# BlueCore_TM_3-Multuimedia_small.net
KiCad netlist of a schematic drawn in EAGLE
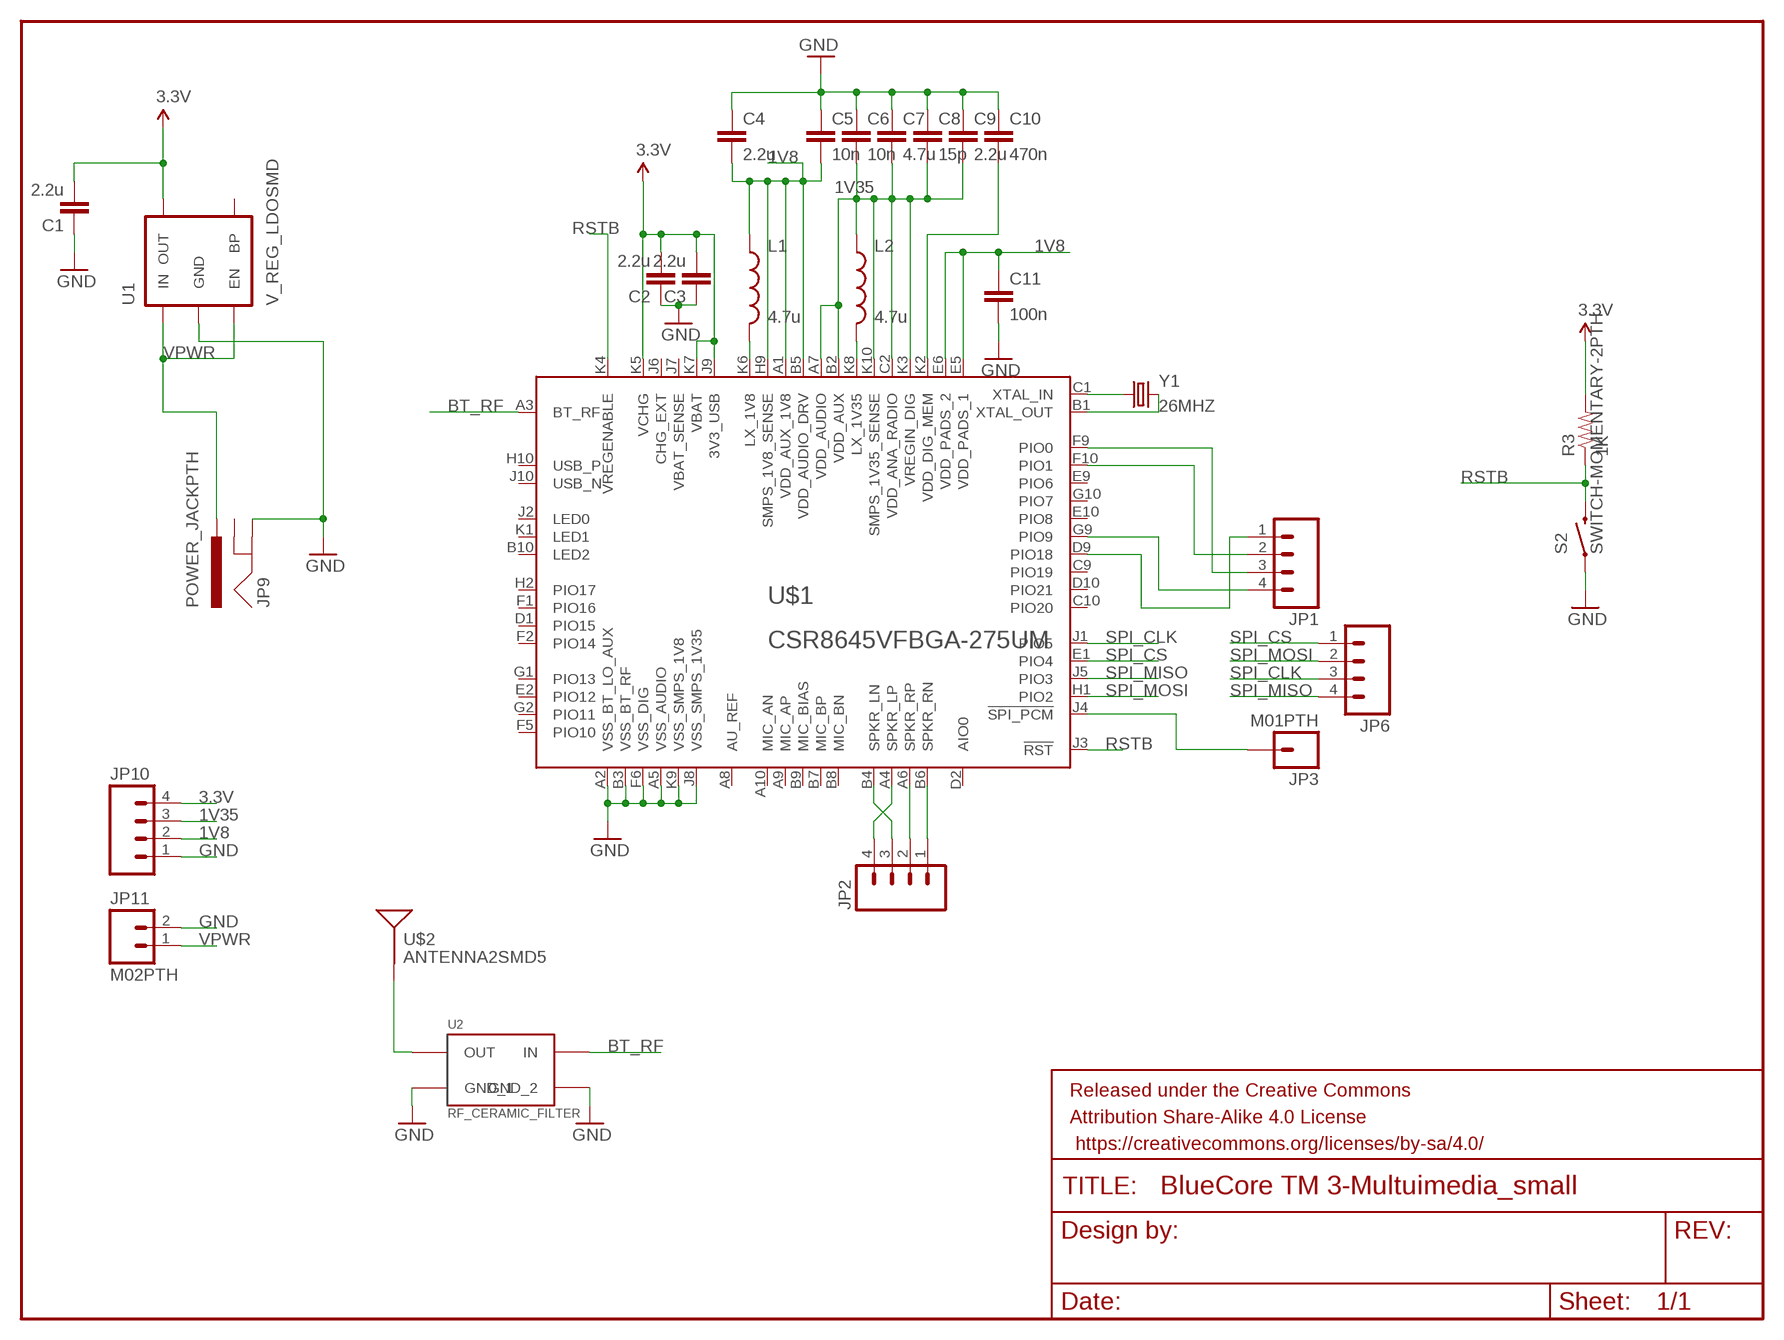
[diagram p0: schematic, sheet 1]

(export (version "E")
  (design (tool "Eeschema 10.0.6"))
  (components
    (comp (ref "C1")
      (value "2.2u")
      (footprint "eagle-import:CAP-PTH-SMALL")
      (libsource (lib "eagle-import") (part "CAPPTH"))
    )
    (comp (ref "C2")
      (value "2.2u")
      (footprint "eagle-import:CAP-PTH-SMALL")
      (libsource (lib "eagle-import") (part "CAPPTH"))
    )
    (comp (ref "C3")
      (value "2.2u")
      (footprint "eagle-import:CAP-PTH-SMALL")
      (libsource (lib "eagle-import") (part "CAPPTH"))
    )
    (comp (ref "C4")
      (value "2.2u")
      (footprint "eagle-import:CAP-PTH-SMALL")
      (libsource (lib "eagle-import") (part "CAPPTH"))
    )
    (comp (ref "C5")
      (value "10n")
      (footprint "eagle-import:CAP-PTH-SMALL")
      (libsource (lib "eagle-import") (part "CAPPTH"))
    )
    (comp (ref "C6")
      (value "10n")
      (footprint "eagle-import:CAP-PTH-SMALL")
      (libsource (lib "eagle-import") (part "CAPPTH"))
    )
    (comp (ref "C7")
      (value "4.7u")
      (footprint "eagle-import:CAP-PTH-SMALL")
      (libsource (lib "eagle-import") (part "CAPPTH"))
    )
    (comp (ref "C8")
      (value "15p")
      (footprint "eagle-import:CAP-PTH-SMALL")
      (libsource (lib "eagle-import") (part "CAPPTH"))
    )
    (comp (ref "C9")
      (value "2.2u")
      (footprint "eagle-import:CAP-PTH-SMALL")
      (libsource (lib "eagle-import") (part "CAPPTH"))
    )
    (comp (ref "C10")
      (value "470n")
      (footprint "eagle-import:CAP-PTH-SMALL")
      (libsource (lib "eagle-import") (part "CAPPTH"))
    )
    (comp (ref "C11")
      (value "100n")
      (footprint "eagle-import:CAP-PTH-SMALL")
      (libsource (lib "eagle-import") (part "CAPPTH"))
    )
    (comp (ref "FRAME1")
      (value "FRAME-LETTER")
      (footprint "eagle-import:CREATIVE_COMMONS")
      (libsource (lib "eagle-import") (part "FRAME-LETTER"))
    )
    (comp (ref "JP1")
      (value "M04PTH")
      (footprint "eagle-import:1X04")
      (libsource (lib "eagle-import") (part "M04PTH"))
    )
    (comp (ref "JP2")
      (value "M04PTH")
      (footprint "eagle-import:1X04")
      (libsource (lib "eagle-import") (part "M04PTH"))
    )
    (comp (ref "JP3")
      (value "M01PTH")
      (footprint "eagle-import:1X01")
      (libsource (lib "eagle-import") (part "M01PTH"))
    )
    (comp (ref "JP6")
      (value "M04PTH")
      (footprint "eagle-import:1X04")
      (libsource (lib "eagle-import") (part "M04PTH"))
    )
    (comp (ref "JP9")
      (value "POWER_JACKPTH")
      (footprint "eagle-import:POWER_JACK_PTH")
      (libsource (lib "eagle-import") (part "POWER_JACKPTH"))
    )
    (comp (ref "JP10")
      (value "M04PTH")
      (footprint "eagle-import:1X04")
      (libsource (lib "eagle-import") (part "M04PTH"))
    )
    (comp (ref "JP11")
      (value "M02PTH")
      (footprint "eagle-import:1X02")
      (libsource (lib "eagle-import") (part "M02PTH"))
    )
    (comp (ref "L1")
      (value "4.7u")
      (footprint "eagle-import:0805")
      (libsource (lib "eagle-import") (part "INDUCTOR0805"))
    )
    (comp (ref "L2")
      (value "4.7u")
      (footprint "eagle-import:0805")
      (libsource (lib "eagle-import") (part "INDUCTOR0805"))
    )
    (comp (ref "R3")
      (value "1K")
      (footprint "eagle-import:0805")
      (libsource (lib "eagle-import") (part "RESISTOR0805-RES"))
    )
    (comp (ref "S2")
      (value "SWITCH-MOMENTARY-2PTH")
      (footprint "eagle-import:TACTILE-PTH")
      (libsource (lib "eagle-import") (part "SWITCH-MOMENTARY-2PTH"))
    )
    (comp (ref "U$1")
      (value "CSR8645VFBGA-275UM")
      (footprint "eagle-import:VFBGA68-LARGE")
      (libsource (lib "eagle-import") (part "CSR8645VFBGA-275UM"))
    )
    (comp (ref "U$2")
      (value "ANTENNA2SMD5")
      (footprint "eagle-import:ANTENNA-CHIP5")
      (libsource (lib "eagle-import") (part "ANTENNA2SMD5"))
    )
    (comp (ref "U1")
      (value "V_REG_LDOSMD")
      (footprint "eagle-import:SOT23-5")
      (libsource (lib "eagle-import") (part "V_REG_LDOSMD"))
    )
    (comp (ref "U2")
      (value "RF_CERAMIC_FILTER")
      (footprint "eagle-import:RF_FILTER")
      (libsource (lib "eagle-import") (part "RF_CERAMIC_FILTER"))
    )
    (comp (ref "Y1")
      (value "26MHZ")
      (footprint "eagle-import:HC49US")
      (libsource (lib "eagle-import") (part "CRYSTALHC49US"))
    )
  )
  (nets
    (net (code "1") (name "/1V8") (class "Default")
      (node (ref "C11") (pin "1") (pinfunction "1_1") (pintype "passive"))
      (node (ref "C4") (pin "2") (pinfunction "2_2") (pintype "passive"))
      (node (ref "C5") (pin "2") (pinfunction "2_2") (pintype "passive"))
      (node (ref "JP10") (pin "2") (pinfunction "2_2") (pintype "passive"))
      (node (ref "L1") (pin "1") (pinfunction "1_1") (pintype "passive"))
      (node (ref "U$1") (pin "A1") (pinfunction "VDD_AUX_1V8_A1") (pintype "bidirectional"))
      (node (ref "U$1") (pin "B5") (pinfunction "VDD_AUDIO_DRV_B5") (pintype "bidirectional"))
      (node (ref "U$1") (pin "E5") (pinfunction "VDD_PADS_1_E5") (pintype "bidirectional"))
      (node (ref "U$1") (pin "E6") (pinfunction "VDD_PADS_2_E6") (pintype "bidirectional"))
      (node (ref "U$1") (pin "H9") (pinfunction "SMPS_1V8_SENSE_H9") (pintype "bidirectional"))
    )
    (net (code "2") (name "/1V35") (class "Default")
      (node (ref "C6") (pin "2") (pinfunction "2_2") (pintype "passive"))
      (node (ref "C7") (pin "2") (pinfunction "2_2") (pintype "passive"))
      (node (ref "C8") (pin "2") (pinfunction "2_2") (pintype "passive"))
      (node (ref "C9") (pin "2") (pinfunction "2_2") (pintype "passive"))
      (node (ref "JP10") (pin "3") (pinfunction "3_3") (pintype "passive"))
      (node (ref "L2") (pin "1") (pinfunction "1_1") (pintype "passive"))
      (node (ref "U$1") (pin "A7") (pinfunction "VDD_AUDIO_A7") (pintype "bidirectional"))
      (node (ref "U$1") (pin "B2") (pinfunction "VDD_AUX_B2") (pintype "bidirectional"))
      (node (ref "U$1") (pin "C2") (pinfunction "VDD_ANA_RADIO_C2") (pintype "bidirectional"))
      (node (ref "U$1") (pin "K10") (pinfunction "SMPS_1V35_SENSE_K10") (pintype "bidirectional"))
      (node (ref "U$1") (pin "K3") (pinfunction "VREGIN_DIG_K3") (pintype "bidirectional"))
    )
    (net (code "3") (name "/BT_RF") (class "Default")
      (node (ref "U$1") (pin "A3") (pinfunction "BT_RF_A3") (pintype "bidirectional"))
      (node (ref "U2") (pin "4") (pinfunction "IN_4") (pintype "bidirectional"))
    )
    (net (code "4") (name "/RSTB") (class "Default")
      (node (ref "R3") (pin "1") (pinfunction "1_1") (pintype "passive"))
      (node (ref "S2") (pin "3") (pinfunction "2_3") (pintype "passive"))
      (node (ref "U$1") (pin "J3") (pinfunction "~{RST}_J3") (pintype "input"))
      (node (ref "U$1") (pin "K4") (pinfunction "VREGENABLE_K4") (pintype "bidirectional"))
    )
    (net (code "5") (name "/SPI_CLK") (class "Default")
      (node (ref "JP6") (pin "3") (pinfunction "3_3") (pintype "passive"))
      (node (ref "U$1") (pin "J1") (pinfunction "PIO5_J1") (pintype "bidirectional"))
    )
    (net (code "6") (name "/SPI_CS") (class "Default")
      (node (ref "JP6") (pin "1") (pinfunction "1_1") (pintype "passive"))
      (node (ref "U$1") (pin "E1") (pinfunction "PIO4_E1") (pintype "bidirectional"))
    )
    (net (code "7") (name "/SPI_MISO") (class "Default")
      (node (ref "JP6") (pin "4") (pinfunction "4_4") (pintype "passive"))
      (node (ref "U$1") (pin "J5") (pinfunction "PIO3_J5") (pintype "bidirectional"))
    )
    (net (code "8") (name "/SPI_MOSI") (class "Default")
      (node (ref "JP6") (pin "2") (pinfunction "2_2") (pintype "passive"))
      (node (ref "U$1") (pin "H1") (pinfunction "PIO2_H1") (pintype "bidirectional"))
    )
    (net (code "9") (name "/VPWR") (class "Default")
      (node (ref "JP11") (pin "1") (pinfunction "1_1") (pintype "passive"))
      (node (ref "JP9") (pin "PWR") (pinfunction "PWR_PWR") (pintype "bidirectional"))
      (node (ref "U1") (pin "1") (pinfunction "IN_1") (pintype "input"))
      (node (ref "U1") (pin "3") (pinfunction "EN_3") (pintype "input"))
    )
    (net (code "10") (name "3.3V") (class "Default")
      (node (ref "C1") (pin "2") (pinfunction "2_2") (pintype "passive"))
      (node (ref "C2") (pin "2") (pinfunction "2_2") (pintype "passive"))
      (node (ref "C3") (pin "2") (pinfunction "2_2") (pintype "passive"))
      (node (ref "JP10") (pin "4") (pinfunction "4_4") (pintype "passive"))
      (node (ref "R3") (pin "2") (pinfunction "2_2") (pintype "passive"))
      (node (ref "U$1") (pin "J9") (pinfunction "3V3_USB_J9") (pintype "power_in"))
      (node (ref "U$1") (pin "K5") (pinfunction "VCHG_K5") (pintype "power_in"))
      (node (ref "U$1") (pin "K7") (pinfunction "VBAT_K7") (pintype "power_in"))
      (node (ref "U1") (pin "5") (pinfunction "OUT_5") (pintype "passive"))
    )
    (net (code "11") (name "GND") (class "Default")
      (node (ref "C1") (pin "1") (pinfunction "1_1") (pintype "passive"))
      (node (ref "C10") (pin "1") (pinfunction "1_1") (pintype "passive"))
      (node (ref "C11") (pin "2") (pinfunction "2_2") (pintype "passive"))
      (node (ref "C2") (pin "1") (pinfunction "1_1") (pintype "passive"))
      (node (ref "C3") (pin "1") (pinfunction "1_1") (pintype "passive"))
      (node (ref "C4") (pin "1") (pinfunction "1_1") (pintype "passive"))
      (node (ref "C5") (pin "1") (pinfunction "1_1") (pintype "passive"))
      (node (ref "C6") (pin "1") (pinfunction "1_1") (pintype "passive"))
      (node (ref "C7") (pin "1") (pinfunction "1_1") (pintype "passive"))
      (node (ref "C8") (pin "1") (pinfunction "1_1") (pintype "passive"))
      (node (ref "C9") (pin "1") (pinfunction "1_1") (pintype "passive"))
      (node (ref "JP10") (pin "1") (pinfunction "1_1") (pintype "passive"))
      (node (ref "JP11") (pin "2") (pinfunction "2_2") (pintype "passive"))
      (node (ref "JP9") (pin "GND") (pinfunction "GND_GND") (pintype "bidirectional"))
      (node (ref "S2") (pin "1") (pinfunction "1_1") (pintype "passive"))
      (node (ref "U$1") (pin "A2") (pinfunction "VSS_BT_LO_AUX_A2") (pintype "bidirectional"))
      (node (ref "U$1") (pin "A5") (pinfunction "VSS_AUDIO_A5") (pintype "bidirectional"))
      (node (ref "U$1") (pin "B3") (pinfunction "VSS_BT_RF_B3") (pintype "bidirectional"))
      (node (ref "U$1") (pin "F6") (pinfunction "VSS_DIG_F6") (pintype "bidirectional"))
      (node (ref "U$1") (pin "J8") (pinfunction "VSS_SMPS_1V35_J8") (pintype "bidirectional"))
      (node (ref "U$1") (pin "K9") (pinfunction "VSS_SMPS_1V8_K9") (pintype "bidirectional"))
      (node (ref "U1") (pin "2") (pinfunction "GND_2") (pintype "input"))
      (node (ref "U2") (pin "1") (pinfunction "GND_1_1") (pintype "power_in"))
      (node (ref "U2") (pin "3") (pinfunction "GND_2_3") (pintype "power_in"))
    )
    (net (code "12") (name "Net-(U$1-LX_1V8)") (class "Default")
      (node (ref "L1") (pin "2") (pinfunction "2_2") (pintype "passive"))
      (node (ref "U$1") (pin "K6") (pinfunction "LX_1V8_K6") (pintype "bidirectional"))
    )
    (net (code "13") (name "Net-(U$1-LX_1V35)") (class "Default")
      (node (ref "L2") (pin "2") (pinfunction "2_2") (pintype "passive"))
      (node (ref "U$1") (pin "K8") (pinfunction "LX_1V35_K8") (pintype "bidirectional"))
    )
    (net (code "14") (name "Net-(U$1-PIO0)") (class "Default")
      (node (ref "JP1") (pin "3") (pinfunction "3_3") (pintype "passive"))
      (node (ref "U$1") (pin "F9") (pinfunction "PIO0_F9") (pintype "bidirectional"))
    )
    (net (code "15") (name "Net-(U$1-PIO1)") (class "Default")
      (node (ref "JP1") (pin "2") (pinfunction "2_2") (pintype "passive"))
      (node (ref "U$1") (pin "F10") (pinfunction "PIO1_F10") (pintype "bidirectional"))
    )
    (net (code "16") (name "Net-(U$1-PIO9)") (class "Default")
      (node (ref "JP1") (pin "4") (pinfunction "4_4") (pintype "passive"))
      (node (ref "U$1") (pin "G9") (pinfunction "PIO9_G9") (pintype "bidirectional"))
    )
    (net (code "17") (name "Net-(U$1-PIO18)") (class "Default")
      (node (ref "JP1") (pin "1") (pinfunction "1_1") (pintype "passive"))
      (node (ref "U$1") (pin "D9") (pinfunction "PIO18_D9") (pintype "bidirectional"))
    )
    (net (code "18") (name "Net-(U$1-SPKR_LN)") (class "Default")
      (node (ref "JP2") (pin "3") (pinfunction "3_3") (pintype "passive"))
      (node (ref "U$1") (pin "B4") (pinfunction "SPKR_LN_B4") (pintype "output"))
    )
    (net (code "19") (name "Net-(U$1-SPKR_LP)") (class "Default")
      (node (ref "JP2") (pin "4") (pinfunction "4_4") (pintype "passive"))
      (node (ref "U$1") (pin "A4") (pinfunction "SPKR_LP_A4") (pintype "output"))
    )
    (net (code "20") (name "Net-(U$1-SPKR_RN)") (class "Default")
      (node (ref "JP2") (pin "1") (pinfunction "1_1") (pintype "passive"))
      (node (ref "U$1") (pin "B6") (pinfunction "SPKR_RN_B6") (pintype "output"))
    )
    (net (code "21") (name "Net-(U$1-SPKR_RP)") (class "Default")
      (node (ref "JP2") (pin "2") (pinfunction "2_2") (pintype "passive"))
      (node (ref "U$1") (pin "A6") (pinfunction "SPKR_RP_A6") (pintype "output"))
    )
    (net (code "22") (name "Net-(U$1-VDD_DIG_MEM)") (class "Default")
      (node (ref "C10") (pin "2") (pinfunction "2_2") (pintype "passive"))
      (node (ref "U$1") (pin "K2") (pinfunction "VDD_DIG_MEM_K2") (pintype "bidirectional"))
    )
    (net (code "23") (name "Net-(U$1-XTAL_IN)") (class "Default")
      (node (ref "U$1") (pin "C1") (pinfunction "XTAL_IN_C1") (pintype "input"))
      (node (ref "Y1") (pin "1") (pinfunction "1_1") (pintype "passive"))
    )
    (net (code "24") (name "Net-(U$1-XTAL_OUT)") (class "Default")
      (node (ref "U$1") (pin "B1") (pinfunction "XTAL_OUT_B1") (pintype "bidirectional"))
      (node (ref "Y1") (pin "2") (pinfunction "2_2") (pintype "passive"))
    )
    (net (code "25") (name "Net-(U$1-~{SPI_PCM})") (class "Default")
      (node (ref "JP3") (pin "1") (pinfunction "1_1") (pintype "passive"))
      (node (ref "U$1") (pin "J4") (pinfunction "~{SPI_PCM}_J4") (pintype "input"))
    )
    (net (code "26") (name "Net-(U$2-SIGNAL)") (class "Default")
      (node (ref "U$2") (pin "FEED") (pinfunction "SIGNAL_FEED") (pintype "bidirectional"))
      (node (ref "U2") (pin "2") (pinfunction "OUT_2") (pintype "bidirectional"))
    )
    (net (code "27") (name "unconnected-(JP9-PadGNDBREAK)") (class "Default")
      (node (ref "JP9") (pin "GNDBREAK") (pinfunction "GNDBREAK_GNDBREAK") (pintype "bidirectional"))
    )
    (net (code "28") (name "unconnected-(U$1-AIO0-PadD2)") (class "Default")
      (node (ref "U$1") (pin "D2") (pinfunction "AIO0_D2") (pintype "bidirectional"))
    )
    (net (code "29") (name "unconnected-(U$1-AU_REF-PadA8)") (class "Default")
      (node (ref "U$1") (pin "A8") (pinfunction "AU_REF_A8") (pintype "input"))
    )
    (net (code "30") (name "unconnected-(U$1-CHG_EXT-PadJ6)") (class "Default")
      (node (ref "U$1") (pin "J6") (pinfunction "CHG_EXT_J6") (pintype "bidirectional"))
    )
    (net (code "31") (name "unconnected-(U$1-LED0-PadJ2)") (class "Default")
      (node (ref "U$1") (pin "J2") (pinfunction "LED0_J2") (pintype "bidirectional"))
    )
    (net (code "32") (name "unconnected-(U$1-LED1-PadK1)") (class "Default")
      (node (ref "U$1") (pin "K1") (pinfunction "LED1_K1") (pintype "bidirectional"))
    )
    (net (code "33") (name "unconnected-(U$1-LED2-PadB10)") (class "Default")
      (node (ref "U$1") (pin "B10") (pinfunction "LED2_B10") (pintype "bidirectional"))
    )
    (net (code "34") (name "unconnected-(U$1-MIC_AN-PadA10)") (class "Default")
      (node (ref "U$1") (pin "A10") (pinfunction "MIC_AN_A10") (pintype "input"))
    )
    (net (code "35") (name "unconnected-(U$1-MIC_AP-PadA9)") (class "Default")
      (node (ref "U$1") (pin "A9") (pinfunction "MIC_AP_A9") (pintype "input"))
    )
    (net (code "36") (name "unconnected-(U$1-MIC_BIAS-PadB9)") (class "Default")
      (node (ref "U$1") (pin "B9") (pinfunction "MIC_BIAS_B9") (pintype "output"))
    )
    (net (code "37") (name "unconnected-(U$1-MIC_BN-PadB8)") (class "Default")
      (node (ref "U$1") (pin "B8") (pinfunction "MIC_BN_B8") (pintype "input"))
    )
    (net (code "38") (name "unconnected-(U$1-MIC_BP-PadB7)") (class "Default")
      (node (ref "U$1") (pin "B7") (pinfunction "MIC_BP_B7") (pintype "input"))
    )
    (net (code "39") (name "unconnected-(U$1-PIO6-PadE9)") (class "Default")
      (node (ref "U$1") (pin "E9") (pinfunction "PIO6_E9") (pintype "bidirectional"))
    )
    (net (code "40") (name "unconnected-(U$1-PIO7-PadG10)") (class "Default")
      (node (ref "U$1") (pin "G10") (pinfunction "PIO7_G10") (pintype "bidirectional"))
    )
    (net (code "41") (name "unconnected-(U$1-PIO8-PadE10)") (class "Default")
      (node (ref "U$1") (pin "E10") (pinfunction "PIO8_E10") (pintype "bidirectional"))
    )
    (net (code "42") (name "unconnected-(U$1-PIO10-PadF5)") (class "Default")
      (node (ref "U$1") (pin "F5") (pinfunction "PIO10_F5") (pintype "bidirectional"))
    )
    (net (code "43") (name "unconnected-(U$1-PIO11-PadG2)") (class "Default")
      (node (ref "U$1") (pin "G2") (pinfunction "PIO11_G2") (pintype "bidirectional"))
    )
    (net (code "44") (name "unconnected-(U$1-PIO12-PadE2)") (class "Default")
      (node (ref "U$1") (pin "E2") (pinfunction "PIO12_E2") (pintype "bidirectional"))
    )
    (net (code "45") (name "unconnected-(U$1-PIO13-PadG1)") (class "Default")
      (node (ref "U$1") (pin "G1") (pinfunction "PIO13_G1") (pintype "bidirectional"))
    )
    (net (code "46") (name "unconnected-(U$1-PIO14-PadF2)") (class "Default")
      (node (ref "U$1") (pin "F2") (pinfunction "PIO14_F2") (pintype "bidirectional"))
    )
    (net (code "47") (name "unconnected-(U$1-PIO15-PadD1)") (class "Default")
      (node (ref "U$1") (pin "D1") (pinfunction "PIO15_D1") (pintype "bidirectional"))
    )
    (net (code "48") (name "unconnected-(U$1-PIO16-PadF1)") (class "Default")
      (node (ref "U$1") (pin "F1") (pinfunction "PIO16_F1") (pintype "bidirectional"))
    )
    (net (code "49") (name "unconnected-(U$1-PIO17-PadH2)") (class "Default")
      (node (ref "U$1") (pin "H2") (pinfunction "PIO17_H2") (pintype "bidirectional"))
    )
    (net (code "50") (name "unconnected-(U$1-PIO19-PadC9)") (class "Default")
      (node (ref "U$1") (pin "C9") (pinfunction "PIO19_C9") (pintype "bidirectional"))
    )
    (net (code "51") (name "unconnected-(U$1-PIO20-PadC10)") (class "Default")
      (node (ref "U$1") (pin "C10") (pinfunction "PIO20_C10") (pintype "bidirectional"))
    )
    (net (code "52") (name "unconnected-(U$1-PIO21-PadD10)") (class "Default")
      (node (ref "U$1") (pin "D10") (pinfunction "PIO21_D10") (pintype "bidirectional"))
    )
    (net (code "53") (name "unconnected-(U$1-USB_N-PadJ10)") (class "Default")
      (node (ref "U$1") (pin "J10") (pinfunction "USB_N_J10") (pintype "bidirectional"))
    )
    (net (code "54") (name "unconnected-(U$1-USB_P-PadH10)") (class "Default")
      (node (ref "U$1") (pin "H10") (pinfunction "USB_P_H10") (pintype "bidirectional"))
    )
    (net (code "55") (name "unconnected-(U$1-VBAT_SENSE-PadJ7)") (class "Default")
      (node (ref "U$1") (pin "J7") (pinfunction "VBAT_SENSE_J7") (pintype "bidirectional"))
    )
    (net (code "56") (name "unconnected-(U1-BP-Pad4)") (class "Default")
      (node (ref "U1") (pin "4") (pinfunction "BP_4") (pintype "input"))
    )
  )
)
